# sheet_V2.net
KiCad netlist of a schematic drawn in Altium Designer
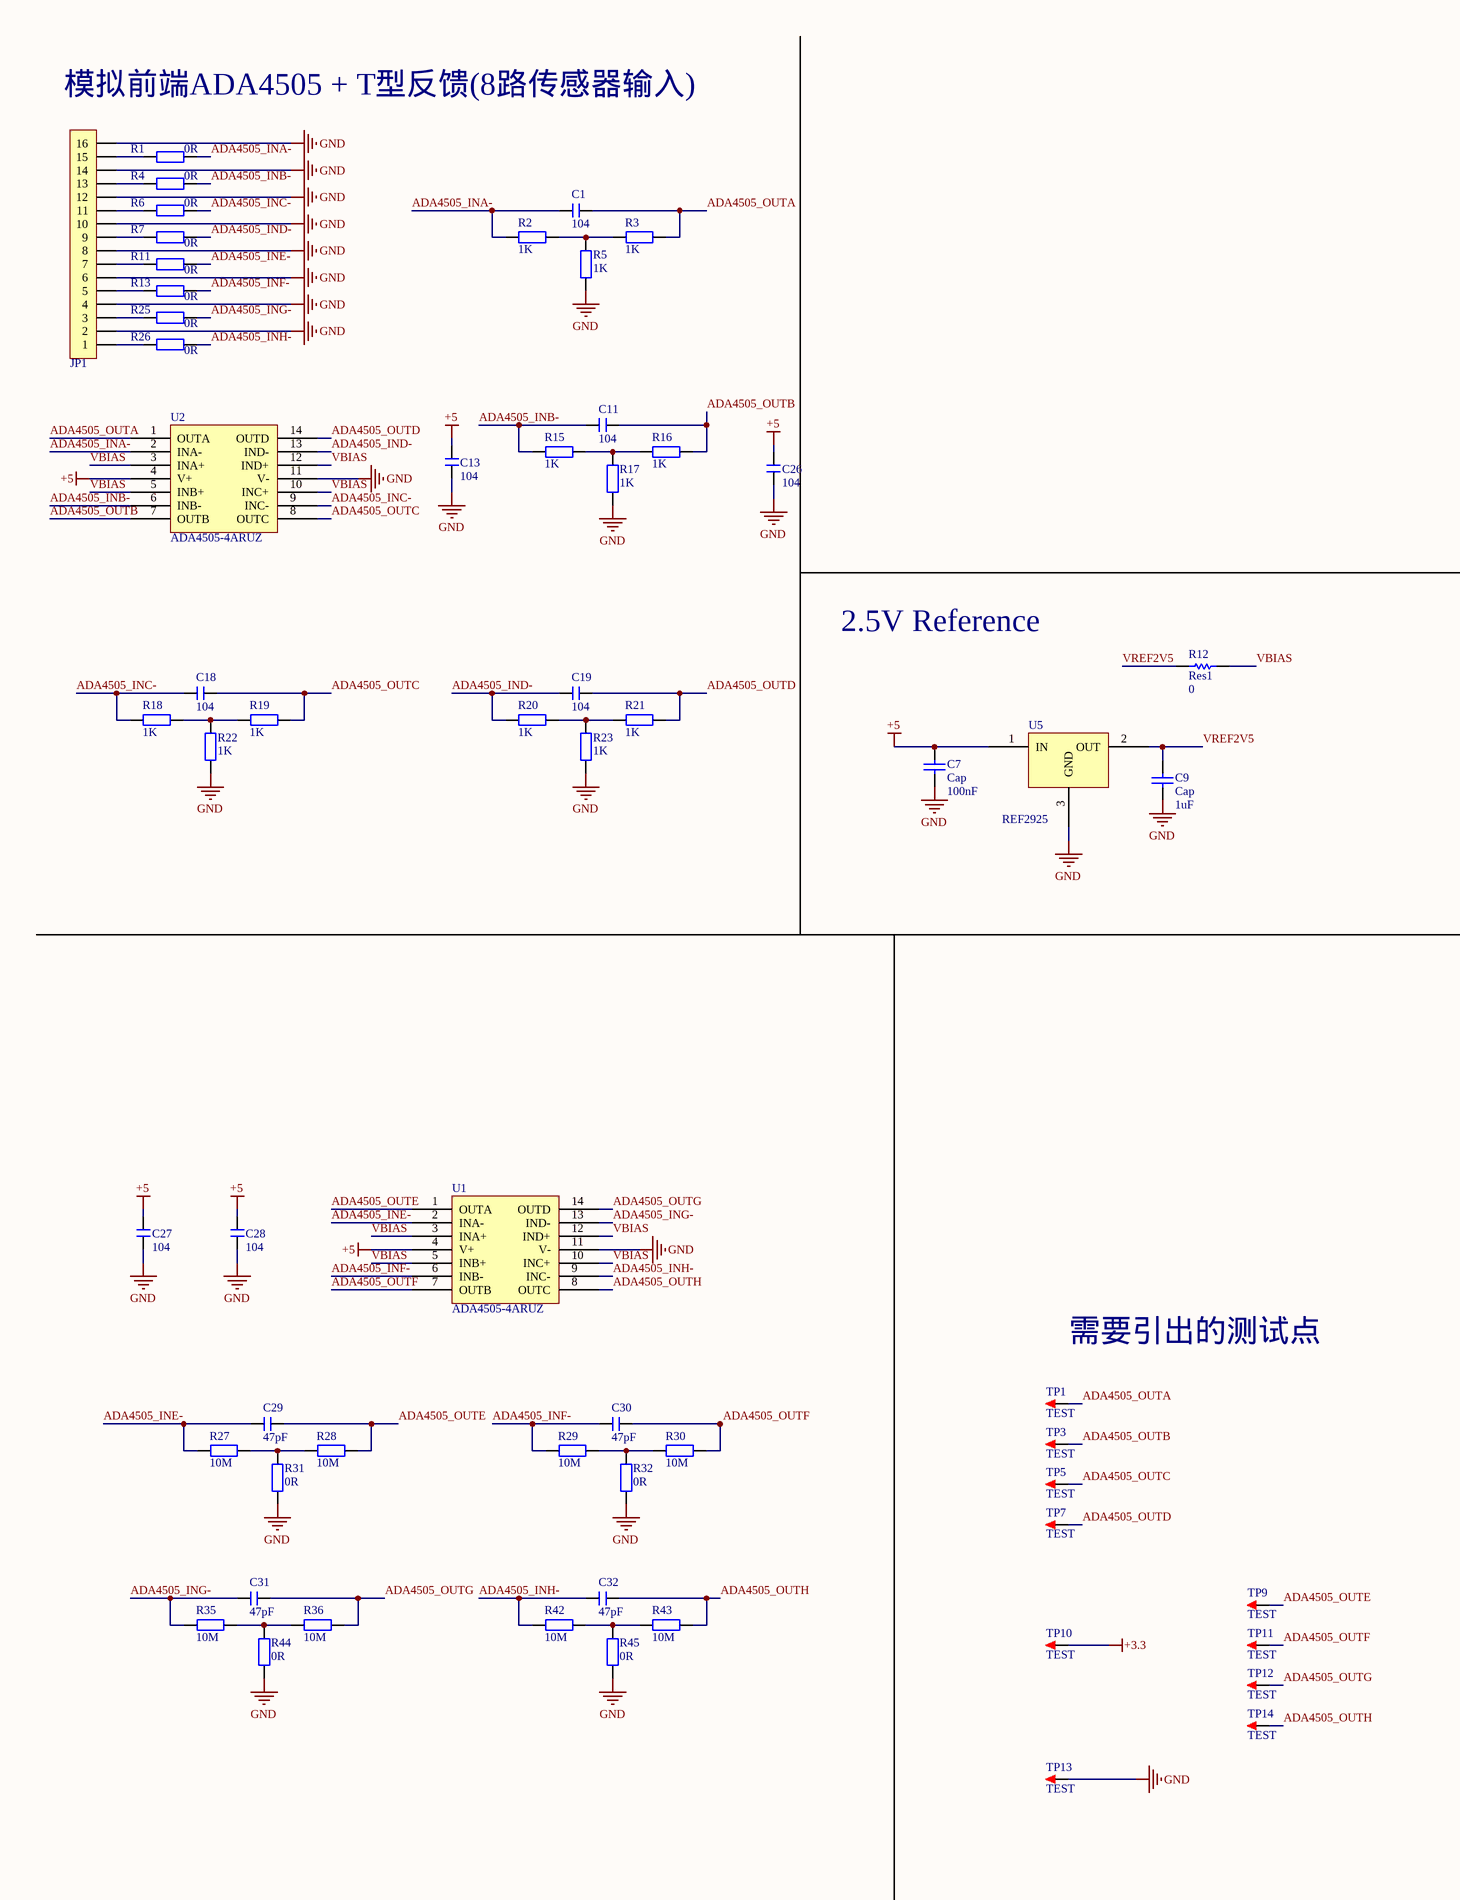
[diagram p0: sheet_V2.SchDoc, left]
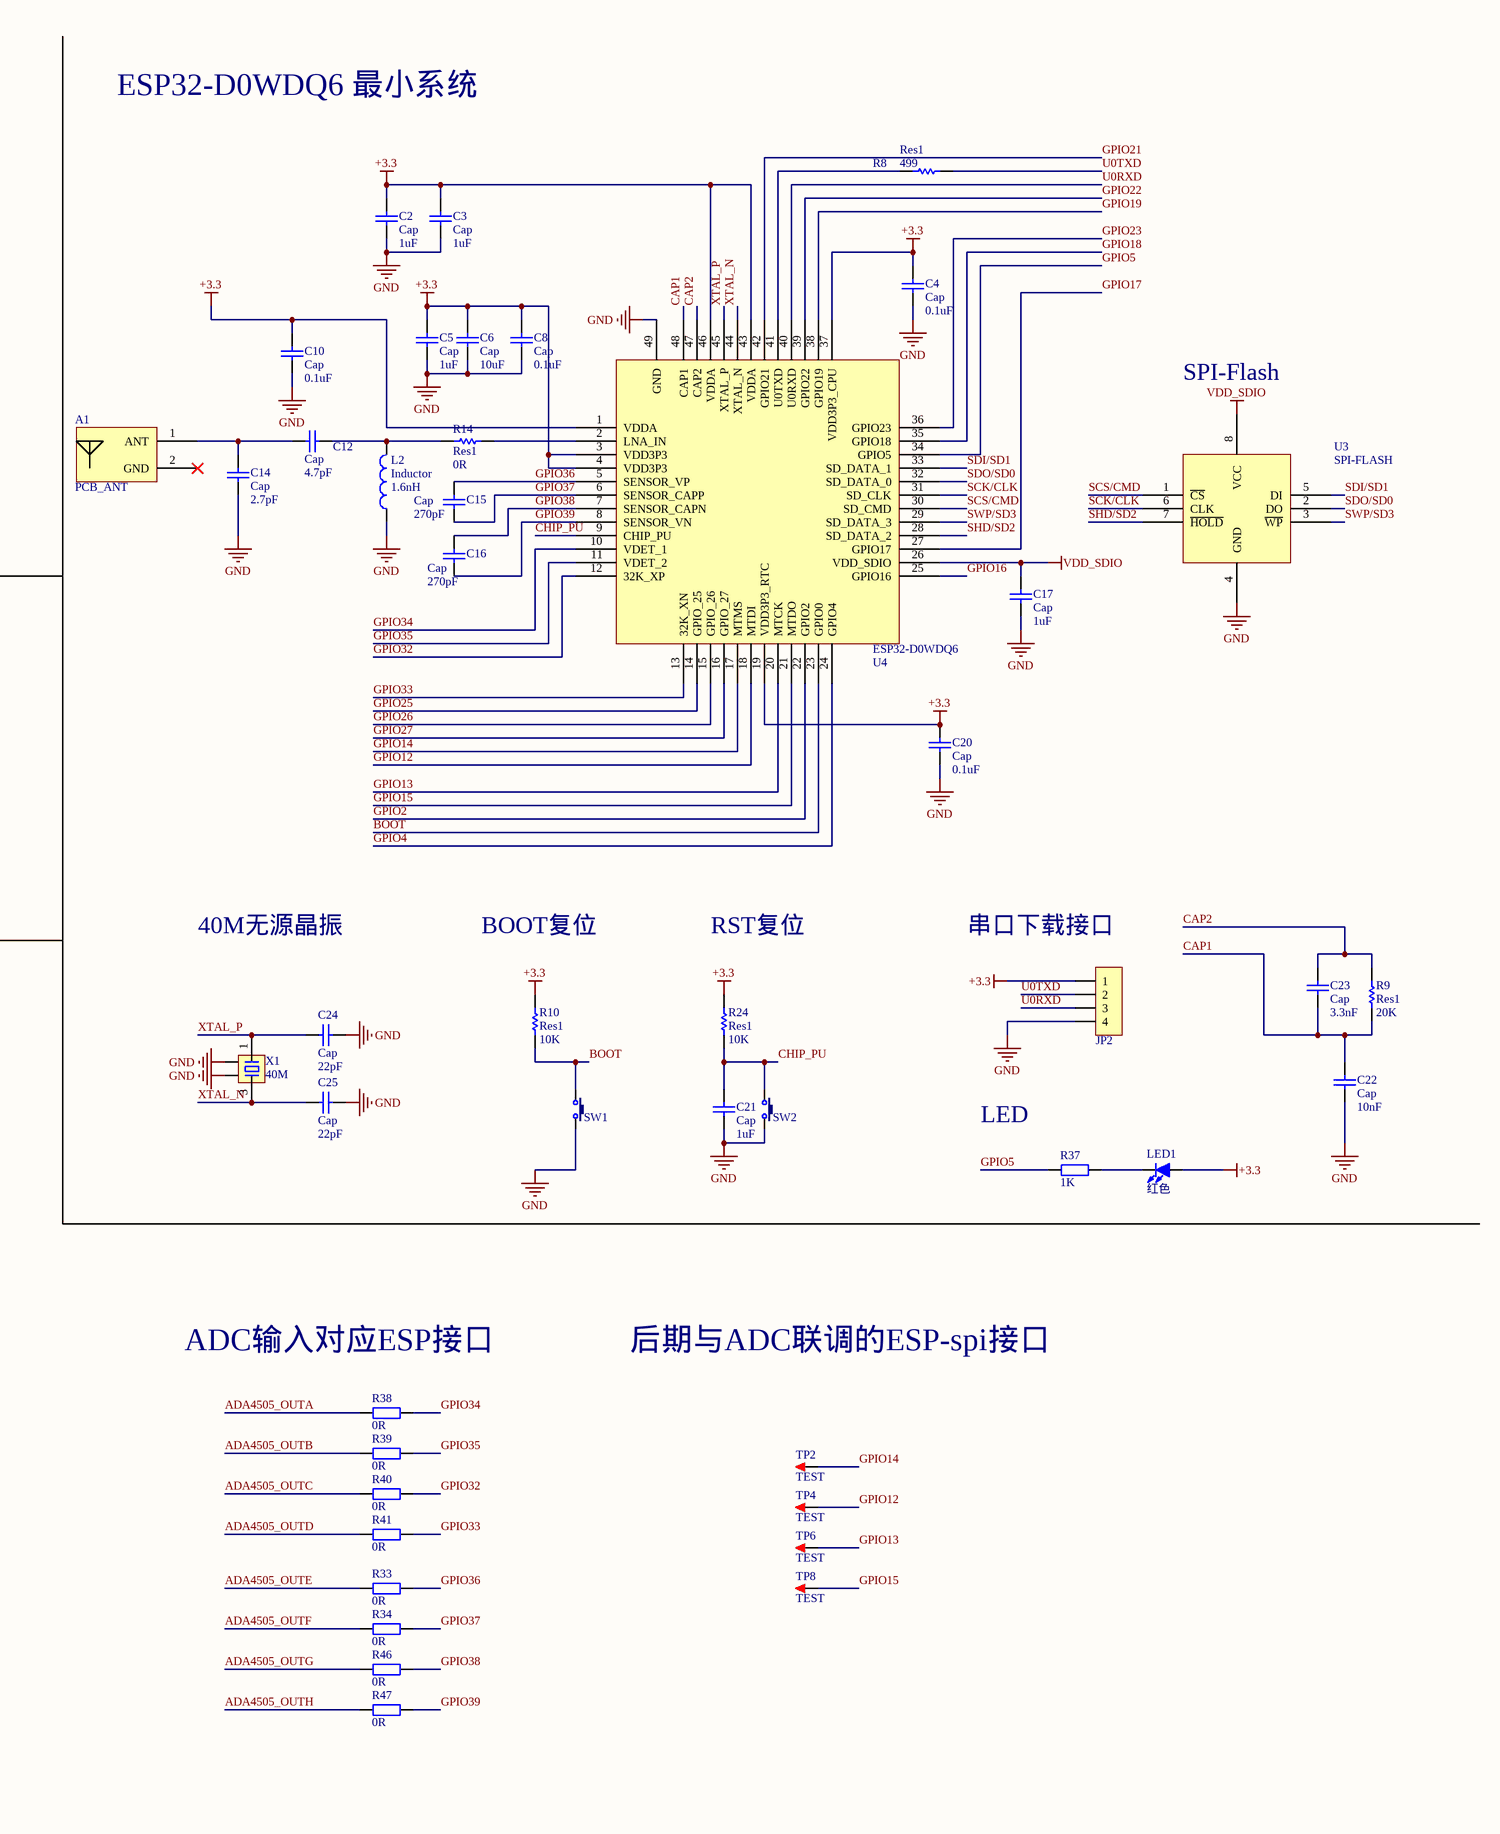
[diagram p1: sheet_V2.SchDoc, right]

(export (version "E")
  (design (tool "Eeschema 10.0.6"))
  (components
    (comp (ref "A1")
      (value "PCB_ANT")
      (footprint "PCB_ANT")
      (description "2.4G-esp32")
      (libsource (lib "Schlib1") (part "PCB_ANT"))
    )
    (comp (ref "C1")
      (value "104")
      (footprint "C 0402_L")
      (description "无极性贴片电容")
      (fields (field (name "版权归属") "源创客"))
      (libsource (lib "Basic_Integrated_Library") (part "C"))
    )
    (comp (ref "C2")
      (value "Cap")
      (footprint "C 0402_L")
      (description "Capacitor")
      (fields (field (name "ALTIUM_VALUE") "1uF") (field (name "PUBLISHER") "Altium Limited"))
      (libsource (lib "Miscellaneous Devices") (part "Cap"))
    )
    (comp (ref "C3")
      (value "Cap")
      (footprint "C 0402_L")
      (description "Capacitor")
      (fields (field (name "ALTIUM_VALUE") "1uF") (field (name "PUBLISHER") "Altium Limited"))
      (libsource (lib "Miscellaneous Devices") (part "Cap"))
    )
    (comp (ref "C4")
      (value "Cap")
      (footprint "C 0402_L")
      (description "Capacitor")
      (fields (field (name "ALTIUM_VALUE") "0.1uF") (field (name "PUBLISHER") "Altium Limited"))
      (libsource (lib "Miscellaneous Devices") (part "Cap"))
    )
    (comp (ref "C5")
      (value "Cap")
      (footprint "C 0402_L")
      (description "Capacitor")
      (fields (field (name "ALTIUM_VALUE") "1uF") (field (name "PUBLISHER") "Altium Limited"))
      (libsource (lib "Miscellaneous Devices") (part "Cap"))
    )
    (comp (ref "C6")
      (value "Cap")
      (footprint "C 0402_L")
      (description "Capacitor")
      (fields (field (name "ALTIUM_VALUE") "10uF") (field (name "PUBLISHER") "Altium Limited"))
      (libsource (lib "Miscellaneous Devices") (part "Cap"))
    )
    (comp (ref "C7")
      (value "Cap")
      (footprint "C 0402_L")
      (description "Capacitor")
      (fields (field (name "ALTIUM_VALUE") "100nF") (field (name "PUBLISHER") "Altium Limited"))
      (libsource (lib "Miscellaneous Devices") (part "Cap"))
    )
    (comp (ref "C8")
      (value "Cap")
      (footprint "C 0402_L")
      (description "Capacitor")
      (fields (field (name "ALTIUM_VALUE") "0.1uF") (field (name "PUBLISHER") "Altium Limited"))
      (libsource (lib "Miscellaneous Devices") (part "Cap"))
    )
    (comp (ref "C9")
      (value "Cap")
      (footprint "C 0402_L")
      (description "Capacitor")
      (fields (field (name "ALTIUM_VALUE") "1uF") (field (name "PUBLISHER") "Altium Limited"))
      (libsource (lib "Miscellaneous Devices") (part "Cap"))
    )
    (comp (ref "C10")
      (value "Cap")
      (footprint "C 0402_L")
      (description "Capacitor")
      (fields (field (name "ALTIUM_VALUE") "0.1uF") (field (name "PUBLISHER") "Altium Limited"))
      (libsource (lib "Miscellaneous Devices") (part "Cap"))
    )
    (comp (ref "C11")
      (value "104")
      (footprint "C 0402_L")
      (description "无极性贴片电容")
      (fields (field (name "版权归属") "源创客"))
      (libsource (lib "Basic_Integrated_Library") (part "C"))
    )
    (comp (ref "C12")
      (value "Cap")
      (footprint "C 0402_L")
      (description "Capacitor")
      (fields (field (name "ALTIUM_VALUE") "4.7pF") (field (name "PUBLISHER") "Altium Limited"))
      (libsource (lib "Miscellaneous Devices") (part "Cap"))
    )
    (comp (ref "C13")
      (value "104")
      (footprint "C 0402_L")
      (description "无极性贴片电容")
      (fields (field (name "版权归属") "源创客"))
      (libsource (lib "Basic_Integrated_Library") (part "C"))
    )
    (comp (ref "C14")
      (value "Cap")
      (footprint "C 0402_L")
      (description "Capacitor")
      (fields (field (name "ALTIUM_VALUE") "2.7pF") (field (name "PUBLISHER") "Altium Limited"))
      (libsource (lib "Miscellaneous Devices") (part "Cap"))
    )
    (comp (ref "C15")
      (value "Cap")
      (footprint "C 0402_L")
      (description "Capacitor")
      (fields (field (name "ALTIUM_VALUE") "270pF") (field (name "PUBLISHER") "Altium Limited"))
      (libsource (lib "Miscellaneous Devices") (part "Cap"))
    )
    (comp (ref "C16")
      (value "Cap")
      (footprint "C 0402_L")
      (description "Capacitor")
      (fields (field (name "ALTIUM_VALUE") "270pF") (field (name "PUBLISHER") "Altium Limited"))
      (libsource (lib "Miscellaneous Devices") (part "Cap"))
    )
    (comp (ref "C17")
      (value "Cap")
      (footprint "C 0402_L")
      (description "Capacitor")
      (fields (field (name "ALTIUM_VALUE") "1uF") (field (name "PUBLISHER") "Altium Limited"))
      (libsource (lib "Miscellaneous Devices") (part "Cap"))
    )
    (comp (ref "C18")
      (value "104")
      (footprint "C 0402_L")
      (description "无极性贴片电容")
      (fields (field (name "版权归属") "源创客"))
      (libsource (lib "Basic_Integrated_Library") (part "C"))
    )
    (comp (ref "C19")
      (value "104")
      (footprint "C 0402_L")
      (description "无极性贴片电容")
      (fields (field (name "版权归属") "源创客"))
      (libsource (lib "Basic_Integrated_Library") (part "C"))
    )
    (comp (ref "C20")
      (value "Cap")
      (footprint "C 0402_L")
      (description "Capacitor")
      (fields (field (name "ALTIUM_VALUE") "0.1uF") (field (name "PUBLISHER") "Altium Limited"))
      (libsource (lib "Miscellaneous Devices") (part "Cap"))
    )
    (comp (ref "C21")
      (value "Cap")
      (footprint "C 0402_L")
      (description "Capacitor")
      (fields (field (name "ALTIUM_VALUE") "1uF") (field (name "PUBLISHER") "Altium Limited"))
      (libsource (lib "Miscellaneous Devices") (part "Cap"))
    )
    (comp (ref "C22")
      (value "Cap")
      (footprint "C 0402_L")
      (description "Capacitor")
      (fields (field (name "ALTIUM_VALUE") "10nF") (field (name "PUBLISHER") "Altium Limited"))
      (libsource (lib "Miscellaneous Devices") (part "Cap"))
    )
    (comp (ref "C23")
      (value "Cap")
      (footprint "C 0402_L")
      (description "Capacitor")
      (fields (field (name "ALTIUM_VALUE") "3.3nF") (field (name "PUBLISHER") "Altium Limited"))
      (libsource (lib "Miscellaneous Devices") (part "Cap"))
    )
    (comp (ref "C24")
      (value "Cap")
      (footprint "C 0402_L")
      (description "Capacitor")
      (fields (field (name "ALTIUM_VALUE") "22pF") (field (name "PUBLISHER") "Altium Limited"))
      (libsource (lib "Miscellaneous Devices") (part "Cap"))
    )
    (comp (ref "C25")
      (value "Cap")
      (footprint "C 0402_L")
      (description "Capacitor")
      (fields (field (name "ALTIUM_VALUE") "22pF") (field (name "PUBLISHER") "Altium Limited"))
      (libsource (lib "Miscellaneous Devices") (part "Cap"))
    )
    (comp (ref "C26")
      (value "104")
      (footprint "C 0402_L")
      (description "无极性贴片电容")
      (fields (field (name "版权归属") "源创客"))
      (libsource (lib "Basic_Integrated_Library") (part "C"))
    )
    (comp (ref "C27")
      (value "104")
      (footprint "C 0402_L")
      (description "无极性贴片电容")
      (fields (field (name "版权归属") "源创客"))
      (libsource (lib "Basic_Integrated_Library") (part "C"))
    )
    (comp (ref "C28")
      (value "104")
      (footprint "C 0402_L")
      (description "无极性贴片电容")
      (fields (field (name "版权归属") "源创客"))
      (libsource (lib "Basic_Integrated_Library") (part "C"))
    )
    (comp (ref "C29")
      (value "47pF")
      (footprint "C 0402_L")
      (description "无极性贴片电容")
      (fields (field (name "版权归属") "源创客"))
      (libsource (lib "Basic_Integrated_Library") (part "C"))
    )
    (comp (ref "C30")
      (value "47pF")
      (footprint "C 0402_L")
      (description "无极性贴片电容")
      (fields (field (name "版权归属") "源创客"))
      (libsource (lib "Basic_Integrated_Library") (part "C"))
    )
    (comp (ref "C31")
      (value "47pF")
      (footprint "C 0402_L")
      (description "无极性贴片电容")
      (fields (field (name "版权归属") "源创客"))
      (libsource (lib "Basic_Integrated_Library") (part "C"))
    )
    (comp (ref "C32")
      (value "47pF")
      (footprint "C 0402_L")
      (description "无极性贴片电容")
      (fields (field (name "版权归属") "源创客"))
      (libsource (lib "Basic_Integrated_Library") (part "C"))
    )
    (comp (ref "JP1")
      (value "HDR-1X16")
      (footprint "FPC0.5 2H-WS-16P")
      (description "16P接插件")
      (fields (field (name "版权归属") "源创客"))
      (libsource (lib "Basic_Integrated_Library") (part "Header 16"))
    )
    (comp (ref "JP2")
      (value "HDR-1X4")
      (footprint "2.54_pad_4")
      (description "4P接插件")
      (fields (field (name "版权归属") "源创客"))
      (libsource (lib "Basic_Integrated_Library") (part "Header 4"))
    )
    (comp (ref "L2")
      (value "Inductor")
      (footprint "L 0402")
      (fields (field (name "ALTIUM_VALUE") "1.6nH") (field (name "PUBLISHER") "Altium Limited"))
      (libsource (lib "Miscellaneous Devices") (part "Inductor"))
    )
    (comp (ref "LED1")
      (value "红色")
      (footprint "LED 0603R")
      (description "贴片LED")
      (fields (field (name "版权归属") "源创客"))
      (libsource (lib "Basic_Integrated_Library") (part "LED-SMD"))
    )
    (comp (ref "R1")
      (value "0R")
      (footprint "R 0402_L")
      (description "贴片电阻")
      (fields (field (name "版权归属") "源创客"))
      (libsource (lib "Basic_Integrated_Library") (part "R"))
    )
    (comp (ref "R2")
      (value "1K")
      (footprint "R 0805_L")
      (description "贴片电阻")
      (fields (field (name "版权归属") "源创客"))
      (libsource (lib "Basic_Integrated_Library") (part "R"))
    )
    (comp (ref "R3")
      (value "1K")
      (footprint "R 0805_L")
      (description "贴片电阻")
      (fields (field (name "版权归属") "源创客"))
      (libsource (lib "Basic_Integrated_Library") (part "R"))
    )
    (comp (ref "R4")
      (value "0R")
      (footprint "R 0402_L")
      (description "贴片电阻")
      (fields (field (name "版权归属") "源创客"))
      (libsource (lib "Basic_Integrated_Library") (part "R"))
    )
    (comp (ref "R5")
      (value "1K")
      (footprint "R 0805_L")
      (description "贴片电阻")
      (fields (field (name "版权归属") "源创客"))
      (libsource (lib "Basic_Integrated_Library") (part "R"))
    )
    (comp (ref "R6")
      (value "0R")
      (footprint "R 0402_L")
      (description "贴片电阻")
      (fields (field (name "版权归属") "源创客"))
      (libsource (lib "Basic_Integrated_Library") (part "R"))
    )
    (comp (ref "R7")
      (value "0R")
      (footprint "R 0402_L")
      (description "贴片电阻")
      (fields (field (name "版权归属") "源创客"))
      (libsource (lib "Basic_Integrated_Library") (part "R"))
    )
    (comp (ref "R8")
      (value "Res1")
      (footprint "R 0402_L")
      (description "Resistor")
      (fields (field (name "ALTIUM_VALUE") "499") (field (name "PUBLISHER") "Altium Limited"))
      (libsource (lib "Miscellaneous Devices") (part "Res1"))
    )
    (comp (ref "R9")
      (value "Res1")
      (footprint "R 0402_L")
      (description "Resistor")
      (fields (field (name "ALTIUM_VALUE") "20K") (field (name "PUBLISHER") "Altium Limited"))
      (libsource (lib "Miscellaneous Devices") (part "Res1"))
    )
    (comp (ref "R10")
      (value "Res1")
      (footprint "R 0402_L")
      (description "Resistor")
      (fields (field (name "ALTIUM_VALUE") "10K") (field (name "PUBLISHER") "Altium Limited"))
      (libsource (lib "Miscellaneous Devices") (part "Res1"))
    )
    (comp (ref "R11")
      (value "0R")
      (footprint "R 0402_L")
      (description "贴片电阻")
      (fields (field (name "版权归属") "源创客"))
      (libsource (lib "Basic_Integrated_Library") (part "R"))
    )
    (comp (ref "R12")
      (value "Res1")
      (footprint "R 0402_L")
      (description "Resistor")
      (fields (field (name "ALTIUM_VALUE") "0") (field (name "PUBLISHER") "Altium Limited"))
      (libsource (lib "Miscellaneous Devices") (part "Res1"))
    )
    (comp (ref "R13")
      (value "0R")
      (footprint "R 0402_L")
      (description "贴片电阻")
      (fields (field (name "版权归属") "源创客"))
      (libsource (lib "Basic_Integrated_Library") (part "R"))
    )
    (comp (ref "R14")
      (value "Res1")
      (footprint "R 0402_L")
      (description "Resistor")
      (fields (field (name "ALTIUM_VALUE") "0R") (field (name "PUBLISHER") "Altium Limited"))
      (libsource (lib "Miscellaneous Devices") (part "Res1"))
    )
    (comp (ref "R15")
      (value "1K")
      (footprint "R 0805_L")
      (description "贴片电阻")
      (fields (field (name "版权归属") "源创客"))
      (libsource (lib "Basic_Integrated_Library") (part "R"))
    )
    (comp (ref "R16")
      (value "1K")
      (footprint "R 0805_L")
      (description "贴片电阻")
      (fields (field (name "版权归属") "源创客"))
      (libsource (lib "Basic_Integrated_Library") (part "R"))
    )
    (comp (ref "R17")
      (value "1K")
      (footprint "R 0805_L")
      (description "贴片电阻")
      (fields (field (name "版权归属") "源创客"))
      (libsource (lib "Basic_Integrated_Library") (part "R"))
    )
    (comp (ref "R18")
      (value "1K")
      (footprint "R 0805_L")
      (description "贴片电阻")
      (fields (field (name "版权归属") "源创客"))
      (libsource (lib "Basic_Integrated_Library") (part "R"))
    )
    (comp (ref "R19")
      (value "1K")
      (footprint "R 0805_L")
      (description "贴片电阻")
      (fields (field (name "版权归属") "源创客"))
      (libsource (lib "Basic_Integrated_Library") (part "R"))
    )
    (comp (ref "R20")
      (value "1K")
      (footprint "R 0805_L")
      (description "贴片电阻")
      (fields (field (name "版权归属") "源创客"))
      (libsource (lib "Basic_Integrated_Library") (part "R"))
    )
    (comp (ref "R21")
      (value "1K")
      (footprint "R 0805_L")
      (description "贴片电阻")
      (fields (field (name "版权归属") "源创客"))
      (libsource (lib "Basic_Integrated_Library") (part "R"))
    )
    (comp (ref "R22")
      (value "1K")
      (footprint "R 0805_L")
      (description "贴片电阻")
      (fields (field (name "版权归属") "源创客"))
      (libsource (lib "Basic_Integrated_Library") (part "R"))
    )
    (comp (ref "R23")
      (value "1K")
      (footprint "R 0805_L")
      (description "贴片电阻")
      (fields (field (name "版权归属") "源创客"))
      (libsource (lib "Basic_Integrated_Library") (part "R"))
    )
    (comp (ref "R24")
      (value "Res1")
      (footprint "R 0402_L")
      (description "Resistor")
      (fields (field (name "ALTIUM_VALUE") "10K") (field (name "PUBLISHER") "Altium Limited"))
      (libsource (lib "Miscellaneous Devices") (part "Res1"))
    )
    (comp (ref "R25")
      (value "0R")
      (footprint "R 0402_L")
      (description "贴片电阻")
      (fields (field (name "版权归属") "源创客"))
      (libsource (lib "Basic_Integrated_Library") (part "R"))
    )
    (comp (ref "R26")
      (value "0R")
      (footprint "R 0402_L")
      (description "贴片电阻")
      (fields (field (name "版权归属") "源创客"))
      (libsource (lib "Basic_Integrated_Library") (part "R"))
    )
    (comp (ref "R27")
      (value "10M")
      (footprint "R 0805_L")
      (description "贴片电阻")
      (fields (field (name "版权归属") "源创客"))
      (libsource (lib "Basic_Integrated_Library") (part "R"))
    )
    (comp (ref "R28")
      (value "10M")
      (footprint "R 0805_L")
      (description "贴片电阻")
      (fields (field (name "版权归属") "源创客"))
      (libsource (lib "Basic_Integrated_Library") (part "R"))
    )
    (comp (ref "R29")
      (value "10M")
      (footprint "R 0805_L")
      (description "贴片电阻")
      (fields (field (name "版权归属") "源创客"))
      (libsource (lib "Basic_Integrated_Library") (part "R"))
    )
    (comp (ref "R30")
      (value "10M")
      (footprint "R 0805_L")
      (description "贴片电阻")
      (fields (field (name "版权归属") "源创客"))
      (libsource (lib "Basic_Integrated_Library") (part "R"))
    )
    (comp (ref "R31")
      (value "0R")
      (footprint "R 0805_L")
      (description "贴片电阻")
      (fields (field (name "版权归属") "源创客"))
      (libsource (lib "Basic_Integrated_Library") (part "R"))
    )
    (comp (ref "R32")
      (value "0R")
      (footprint "R 0805_L")
      (description "贴片电阻")
      (fields (field (name "版权归属") "源创客"))
      (libsource (lib "Basic_Integrated_Library") (part "R"))
    )
    (comp (ref "R33")
      (value "0R")
      (footprint "R 0402_L")
      (description "贴片电阻")
      (fields (field (name "版权归属") "源创客"))
      (libsource (lib "Basic_Integrated_Library") (part "R"))
    )
    (comp (ref "R34")
      (value "0R")
      (footprint "R 0402_L")
      (description "贴片电阻")
      (fields (field (name "版权归属") "源创客"))
      (libsource (lib "Basic_Integrated_Library") (part "R"))
    )
    (comp (ref "R35")
      (value "10M")
      (footprint "R 0805_L")
      (description "贴片电阻")
      (fields (field (name "版权归属") "源创客"))
      (libsource (lib "Basic_Integrated_Library") (part "R"))
    )
    (comp (ref "R36")
      (value "10M")
      (footprint "R 0805_L")
      (description "贴片电阻")
      (fields (field (name "版权归属") "源创客"))
      (libsource (lib "Basic_Integrated_Library") (part "R"))
    )
    (comp (ref "R37")
      (value "1K")
      (footprint "R 0402_L")
      (description "贴片电阻")
      (fields (field (name "版权归属") "源创客"))
      (libsource (lib "Basic_Integrated_Library") (part "R"))
    )
    (comp (ref "R38")
      (value "0R")
      (footprint "R 0402_L")
      (description "贴片电阻")
      (fields (field (name "版权归属") "源创客"))
      (libsource (lib "Basic_Integrated_Library") (part "R"))
    )
    (comp (ref "R39")
      (value "0R")
      (footprint "R 0402_L")
      (description "贴片电阻")
      (fields (field (name "版权归属") "源创客"))
      (libsource (lib "Basic_Integrated_Library") (part "R"))
    )
    (comp (ref "R40")
      (value "0R")
      (footprint "R 0402_L")
      (description "贴片电阻")
      (fields (field (name "版权归属") "源创客"))
      (libsource (lib "Basic_Integrated_Library") (part "R"))
    )
    (comp (ref "R41")
      (value "0R")
      (footprint "R 0402_L")
      (description "贴片电阻")
      (fields (field (name "版权归属") "源创客"))
      (libsource (lib "Basic_Integrated_Library") (part "R"))
    )
    (comp (ref "R42")
      (value "10M")
      (footprint "R 0805_L")
      (description "贴片电阻")
      (fields (field (name "版权归属") "源创客"))
      (libsource (lib "Basic_Integrated_Library") (part "R"))
    )
    (comp (ref "R43")
      (value "10M")
      (footprint "R 0805_L")
      (description "贴片电阻")
      (fields (field (name "版权归属") "源创客"))
      (libsource (lib "Basic_Integrated_Library") (part "R"))
    )
    (comp (ref "R44")
      (value "0R")
      (footprint "R 0805_L")
      (description "贴片电阻")
      (fields (field (name "版权归属") "源创客"))
      (libsource (lib "Basic_Integrated_Library") (part "R"))
    )
    (comp (ref "R45")
      (value "0R")
      (footprint "R 0805_L")
      (description "贴片电阻")
      (fields (field (name "版权归属") "源创客"))
      (libsource (lib "Basic_Integrated_Library") (part "R"))
    )
    (comp (ref "R46")
      (value "0R")
      (footprint "R 0402_L")
      (description "贴片电阻")
      (fields (field (name "版权归属") "源创客"))
      (libsource (lib "Basic_Integrated_Library") (part "R"))
    )
    (comp (ref "R47")
      (value "0R")
      (footprint "R 0402_L")
      (description "贴片电阻")
      (fields (field (name "版权归属") "源创客"))
      (libsource (lib "Basic_Integrated_Library") (part "R"))
    )
    (comp (ref "SW1")
      (value "3x6x5")
      (footprint "KEY-little")
      (description "3x6轻触开关")
      (fields (field (name "版权归属") "源创客"))
      (libsource (lib "5.1   - 按键-开关") (part "TSW 3x6"))
    )
    (comp (ref "SW2")
      (value "3x6x5")
      (footprint "KEY-little")
      (description "3x6轻触开关")
      (fields (field (name "版权归属") "源创客"))
      (libsource (lib "5.1   - 按键-开关") (part "TSW 3x6"))
    )
    (comp (ref "TP1")
      (value "TEST")
      (footprint "TEST 0.8")
      (description "测试点")
      (fields (field (name "版权归属") "源创客"))
      (libsource (lib "Basic_Integrated_Library") (part "TEST"))
    )
    (comp (ref "TP2")
      (value "TEST")
      (footprint "TEST 0.8")
      (description "测试点")
      (fields (field (name "版权归属") "源创客"))
      (libsource (lib "Basic_Integrated_Library") (part "TEST"))
    )
    (comp (ref "TP3")
      (value "TEST")
      (footprint "TEST 0.8")
      (description "测试点")
      (fields (field (name "版权归属") "源创客"))
      (libsource (lib "Basic_Integrated_Library") (part "TEST"))
    )
    (comp (ref "TP4")
      (value "TEST")
      (footprint "TEST 0.8")
      (description "测试点")
      (fields (field (name "版权归属") "源创客"))
      (libsource (lib "Basic_Integrated_Library") (part "TEST"))
    )
    (comp (ref "TP5")
      (value "TEST")
      (footprint "TEST 0.8")
      (description "测试点")
      (fields (field (name "版权归属") "源创客"))
      (libsource (lib "Basic_Integrated_Library") (part "TEST"))
    )
    (comp (ref "TP6")
      (value "TEST")
      (footprint "TEST 0.8")
      (description "测试点")
      (fields (field (name "版权归属") "源创客"))
      (libsource (lib "Basic_Integrated_Library") (part "TEST"))
    )
    (comp (ref "TP7")
      (value "TEST")
      (footprint "TEST 0.8")
      (description "测试点")
      (fields (field (name "版权归属") "源创客"))
      (libsource (lib "Basic_Integrated_Library") (part "TEST"))
    )
    (comp (ref "TP8")
      (value "TEST")
      (footprint "TEST 0.8")
      (description "测试点")
      (fields (field (name "版权归属") "源创客"))
      (libsource (lib "Basic_Integrated_Library") (part "TEST"))
    )
    (comp (ref "TP9")
      (value "TEST")
      (footprint "TEST 0.8")
      (description "测试点")
      (fields (field (name "版权归属") "源创客"))
      (libsource (lib "Basic_Integrated_Library") (part "TEST"))
    )
    (comp (ref "TP10")
      (value "TEST")
      (footprint "TEST 0.8")
      (description "测试点")
      (fields (field (name "版权归属") "源创客"))
      (libsource (lib "Basic_Integrated_Library") (part "TEST"))
    )
    (comp (ref "TP11")
      (value "TEST")
      (footprint "TEST 0.8")
      (description "测试点")
      (fields (field (name "版权归属") "源创客"))
      (libsource (lib "Basic_Integrated_Library") (part "TEST"))
    )
    (comp (ref "TP12")
      (value "TEST")
      (footprint "TEST 0.8")
      (description "测试点")
      (fields (field (name "版权归属") "源创客"))
      (libsource (lib "Basic_Integrated_Library") (part "TEST"))
    )
    (comp (ref "TP13")
      (value "TEST")
      (footprint "TEST 0.8")
      (description "测试点")
      (fields (field (name "版权归属") "源创客"))
      (libsource (lib "Basic_Integrated_Library") (part "TEST"))
    )
    (comp (ref "TP14")
      (value "TEST")
      (footprint "TEST 0.8")
      (description "测试点")
      (fields (field (name "版权归属") "源创客"))
      (libsource (lib "Basic_Integrated_Library") (part "TEST"))
    )
    (comp (ref "U1")
      (value "ADA4505-4ARUZ")
      (footprint "ADA4505-4ARUZ")
      (libsource (lib "Schlib1") (part "ADA4505-4ARUZ"))
    )
    (comp (ref "U2")
      (value "ADA4505-4ARUZ")
      (footprint "ADA4505-4ARUZ")
      (libsource (lib "Schlib1") (part "ADA4505-4ARUZ"))
    )
    (comp (ref "U3")
      (value "SPI-FLASH")
      (footprint "SPI-Flash")
      (libsource (lib "Schlib1") (part "SPI-FLASH"))
    )
    (comp (ref "U4")
      (value "ESP32-D0WDQ6")
      (footprint "ESP32D0WDQ6")
      (libsource (lib "Schlib1") (part "ESP32-D0WDQ6"))
    )
    (comp (ref "U5")
      (value "REF2925")
      (footprint "REF2925AIDBZR")
      (description "2.5V reference")
      (libsource (lib "Schlib1") (part "REF2925"))
    )
    (comp (ref "X1")
      (value "40M")
      (footprint "晶振3225")
      (description "4脚无源晶振")
      (fields (field (name "版权归属") "源创客"))
      (libsource (lib "晶体振荡器") (part "XTAL-4P"))
    )
  )
  (nets
    (net (code "1") (name "+3.3") (class "Default")
      (node (ref "C10") (pin "2") (pinfunction "2_2") (pintype "passive"))
      (node (ref "C2") (pin "2") (pinfunction "2_2") (pintype "passive"))
      (node (ref "C20") (pin "2") (pinfunction "2_2") (pintype "passive"))
      (node (ref "C3") (pin "2") (pinfunction "2_2") (pintype "passive"))
      (node (ref "C4") (pin "2") (pinfunction "2_2") (pintype "passive"))
      (node (ref "C5") (pin "2") (pinfunction "2_2") (pintype "passive"))
      (node (ref "C6") (pin "2") (pinfunction "2_2") (pintype "passive"))
      (node (ref "C8") (pin "2") (pinfunction "2_2") (pintype "passive"))
      (node (ref "JP2") (pin "1") (pinfunction "1_1") (pintype "passive"))
      (node (ref "LED1") (pin "1") (pinfunction "A_1") (pintype "passive"))
      (node (ref "R10") (pin "2") (pinfunction "2_2") (pintype "passive"))
      (node (ref "R24") (pin "2") (pinfunction "2_2") (pintype "passive"))
      (node (ref "TP10") (pin "1") (pinfunction "1_1") (pintype "passive"))
      (node (ref "U4") (pin "1") (pinfunction "VDDA_1") (pintype "passive"))
      (node (ref "U4") (pin "19") (pinfunction "VDD3P3_RTC_19") (pintype "passive"))
      (node (ref "U4") (pin "3") (pinfunction "VDD3P3_3") (pintype "passive"))
      (node (ref "U4") (pin "37") (pinfunction "VDD3P3_CPU_37") (pintype "passive"))
      (node (ref "U4") (pin "4") (pinfunction "VDD3P3_4") (pintype "passive"))
      (node (ref "U4") (pin "43") (pinfunction "VDDA_43") (pintype "passive"))
      (node (ref "U4") (pin "46") (pinfunction "VDDA_46") (pintype "passive"))
    )
    (net (code "2") (name "+5") (class "Default")
      (node (ref "C13") (pin "2") (pinfunction "2_2") (pintype "passive"))
      (node (ref "C26") (pin "2") (pinfunction "2_2") (pintype "passive"))
      (node (ref "C27") (pin "2") (pinfunction "2_2") (pintype "passive"))
      (node (ref "C28") (pin "2") (pinfunction "2_2") (pintype "passive"))
      (node (ref "C7") (pin "2") (pinfunction "2_2") (pintype "passive"))
      (node (ref "U1") (pin "4") (pinfunction "V+_4") (pintype "passive"))
      (node (ref "U2") (pin "4") (pinfunction "V+_4") (pintype "passive"))
      (node (ref "U5") (pin "1") (pinfunction "IN_1") (pintype "passive"))
    )
    (net (code "3") (name "/ADA4505_INA-") (class "Default")
      (node (ref "C1") (pin "1") (pinfunction "1_1") (pintype "passive"))
      (node (ref "R1") (pin "2") (pinfunction "2_2") (pintype "passive"))
      (node (ref "R2") (pin "2") (pinfunction "2_2") (pintype "passive"))
      (node (ref "U2") (pin "2") (pinfunction "INA-_2") (pintype "passive"))
    )
    (net (code "4") (name "/ADA4505_INB-") (class "Default")
      (node (ref "C11") (pin "1") (pinfunction "1_1") (pintype "passive"))
      (node (ref "R15") (pin "2") (pinfunction "2_2") (pintype "passive"))
      (node (ref "R4") (pin "2") (pinfunction "2_2") (pintype "passive"))
      (node (ref "U2") (pin "6") (pinfunction "INB-_6") (pintype "passive"))
    )
    (net (code "5") (name "/ADA4505_INC-") (class "Default")
      (node (ref "C18") (pin "1") (pinfunction "1_1") (pintype "passive"))
      (node (ref "R18") (pin "2") (pinfunction "2_2") (pintype "passive"))
      (node (ref "R6") (pin "2") (pinfunction "2_2") (pintype "passive"))
      (node (ref "U2") (pin "9") (pinfunction "INC-_9") (pintype "passive"))
    )
    (net (code "6") (name "/ADA4505_IND-") (class "Default")
      (node (ref "C19") (pin "1") (pinfunction "1_1") (pintype "passive"))
      (node (ref "R20") (pin "2") (pinfunction "2_2") (pintype "passive"))
      (node (ref "R7") (pin "2") (pinfunction "2_2") (pintype "passive"))
      (node (ref "U2") (pin "13") (pinfunction "IND-_13") (pintype "passive"))
    )
    (net (code "7") (name "/ADA4505_INE-") (class "Default")
      (node (ref "C29") (pin "1") (pinfunction "1_1") (pintype "passive"))
      (node (ref "R11") (pin "2") (pinfunction "2_2") (pintype "passive"))
      (node (ref "R27") (pin "2") (pinfunction "2_2") (pintype "passive"))
      (node (ref "U1") (pin "2") (pinfunction "INA-_2") (pintype "passive"))
    )
    (net (code "8") (name "/ADA4505_INF-") (class "Default")
      (node (ref "C30") (pin "1") (pinfunction "1_1") (pintype "passive"))
      (node (ref "R13") (pin "2") (pinfunction "2_2") (pintype "passive"))
      (node (ref "R29") (pin "2") (pinfunction "2_2") (pintype "passive"))
      (node (ref "U1") (pin "6") (pinfunction "INB-_6") (pintype "passive"))
    )
    (net (code "9") (name "/ADA4505_ING-") (class "Default")
      (node (ref "C31") (pin "1") (pinfunction "1_1") (pintype "passive"))
      (node (ref "R25") (pin "2") (pinfunction "2_2") (pintype "passive"))
      (node (ref "R35") (pin "2") (pinfunction "2_2") (pintype "passive"))
      (node (ref "U1") (pin "13") (pinfunction "IND-_13") (pintype "passive"))
    )
    (net (code "10") (name "/ADA4505_INH-") (class "Default")
      (node (ref "C32") (pin "1") (pinfunction "1_1") (pintype "passive"))
      (node (ref "R26") (pin "2") (pinfunction "2_2") (pintype "passive"))
      (node (ref "R42") (pin "2") (pinfunction "2_2") (pintype "passive"))
      (node (ref "U1") (pin "9") (pinfunction "INC-_9") (pintype "passive"))
    )
    (net (code "11") (name "/ADA4505_OUTA") (class "Default")
      (node (ref "C1") (pin "2") (pinfunction "2_2") (pintype "passive"))
      (node (ref "R3") (pin "1") (pinfunction "1_1") (pintype "passive"))
      (node (ref "R38") (pin "1") (pinfunction "1_1") (pintype "passive"))
      (node (ref "TP1") (pin "1") (pinfunction "1_1") (pintype "passive"))
      (node (ref "U2") (pin "1") (pinfunction "OUTA_1") (pintype "passive"))
    )
    (net (code "12") (name "/ADA4505_OUTB") (class "Default")
      (node (ref "C11") (pin "2") (pinfunction "2_2") (pintype "passive"))
      (node (ref "R16") (pin "1") (pinfunction "1_1") (pintype "passive"))
      (node (ref "R39") (pin "1") (pinfunction "1_1") (pintype "passive"))
      (node (ref "TP3") (pin "1") (pinfunction "1_1") (pintype "passive"))
      (node (ref "U2") (pin "7") (pinfunction "OUTB_7") (pintype "passive"))
    )
    (net (code "13") (name "/ADA4505_OUTC") (class "Default")
      (node (ref "C18") (pin "2") (pinfunction "2_2") (pintype "passive"))
      (node (ref "R19") (pin "1") (pinfunction "1_1") (pintype "passive"))
      (node (ref "R40") (pin "1") (pinfunction "1_1") (pintype "passive"))
      (node (ref "TP5") (pin "1") (pinfunction "1_1") (pintype "passive"))
      (node (ref "U2") (pin "8") (pinfunction "OUTC_8") (pintype "passive"))
    )
    (net (code "14") (name "/ADA4505_OUTD") (class "Default")
      (node (ref "C19") (pin "2") (pinfunction "2_2") (pintype "passive"))
      (node (ref "R21") (pin "1") (pinfunction "1_1") (pintype "passive"))
      (node (ref "R41") (pin "1") (pinfunction "1_1") (pintype "passive"))
      (node (ref "TP7") (pin "1") (pinfunction "1_1") (pintype "passive"))
      (node (ref "U2") (pin "14") (pinfunction "OUTD_14") (pintype "passive"))
    )
    (net (code "15") (name "/ADA4505_OUTE") (class "Default")
      (node (ref "C29") (pin "2") (pinfunction "2_2") (pintype "passive"))
      (node (ref "R28") (pin "1") (pinfunction "1_1") (pintype "passive"))
      (node (ref "R33") (pin "1") (pinfunction "1_1") (pintype "passive"))
      (node (ref "TP9") (pin "1") (pinfunction "1_1") (pintype "passive"))
      (node (ref "U1") (pin "1") (pinfunction "OUTA_1") (pintype "passive"))
    )
    (net (code "16") (name "/ADA4505_OUTF") (class "Default")
      (node (ref "C30") (pin "2") (pinfunction "2_2") (pintype "passive"))
      (node (ref "R30") (pin "1") (pinfunction "1_1") (pintype "passive"))
      (node (ref "R34") (pin "1") (pinfunction "1_1") (pintype "passive"))
      (node (ref "TP11") (pin "1") (pinfunction "1_1") (pintype "passive"))
      (node (ref "U1") (pin "7") (pinfunction "OUTB_7") (pintype "passive"))
    )
    (net (code "17") (name "/ADA4505_OUTG") (class "Default")
      (node (ref "C31") (pin "2") (pinfunction "2_2") (pintype "passive"))
      (node (ref "R36") (pin "1") (pinfunction "1_1") (pintype "passive"))
      (node (ref "R46") (pin "1") (pinfunction "1_1") (pintype "passive"))
      (node (ref "TP12") (pin "1") (pinfunction "1_1") (pintype "passive"))
      (node (ref "U1") (pin "14") (pinfunction "OUTD_14") (pintype "passive"))
    )
    (net (code "18") (name "/ADA4505_OUTH") (class "Default")
      (node (ref "C32") (pin "2") (pinfunction "2_2") (pintype "passive"))
      (node (ref "R43") (pin "1") (pinfunction "1_1") (pintype "passive"))
      (node (ref "R47") (pin "1") (pinfunction "1_1") (pintype "passive"))
      (node (ref "TP14") (pin "1") (pinfunction "1_1") (pintype "passive"))
      (node (ref "U1") (pin "8") (pinfunction "OUTC_8") (pintype "passive"))
    )
    (net (code "19") (name "/BOOT") (class "Default")
      (node (ref "R10") (pin "1") (pinfunction "1_1") (pintype "passive"))
      (node (ref "SW1") (pin "1") (pinfunction "1_1") (pintype "passive"))
      (node (ref "U4") (pin "23") (pinfunction "GPIO0_23") (pintype "passive"))
    )
    (net (code "20") (name "/CAP1") (class "Default")
      (node (ref "C22") (pin "2") (pinfunction "2_2") (pintype "passive"))
      (node (ref "C23") (pin "1") (pinfunction "1_1") (pintype "passive"))
      (node (ref "R9") (pin "1") (pinfunction "1_1") (pintype "passive"))
      (node (ref "U4") (pin "48") (pinfunction "CAP1_48") (pintype "passive"))
    )
    (net (code "21") (name "/CAP2") (class "Default")
      (node (ref "C23") (pin "2") (pinfunction "2_2") (pintype "passive"))
      (node (ref "R9") (pin "2") (pinfunction "2_2") (pintype "passive"))
      (node (ref "U4") (pin "47") (pinfunction "CAP2_47") (pintype "passive"))
    )
    (net (code "22") (name "/CHIP_PU") (class "Default")
      (node (ref "C21") (pin "2") (pinfunction "2_2") (pintype "passive"))
      (node (ref "R24") (pin "1") (pinfunction "1_1") (pintype "passive"))
      (node (ref "SW2") (pin "1") (pinfunction "1_1") (pintype "passive"))
      (node (ref "U4") (pin "9") (pinfunction "CHIP_PU_9") (pintype "passive"))
    )
    (net (code "23") (name "/GPIO2") (class "Default")
      (node (ref "U4") (pin "22") (pinfunction "GPIO2_22") (pintype "passive"))
    )
    (net (code "24") (name "/GPIO4") (class "Default")
      (node (ref "U4") (pin "24") (pinfunction "GPIO4_24") (pintype "passive"))
    )
    (net (code "25") (name "/GPIO5") (class "Default")
      (node (ref "R37") (pin "1") (pinfunction "1_1") (pintype "passive"))
      (node (ref "U4") (pin "34") (pinfunction "GPIO5_34") (pintype "passive"))
    )
    (net (code "26") (name "/GPIO12") (class "Default")
      (node (ref "TP4") (pin "1") (pinfunction "1_1") (pintype "passive"))
      (node (ref "U4") (pin "18") (pinfunction "MTDI_18") (pintype "passive"))
    )
    (net (code "27") (name "/GPIO13") (class "Default")
      (node (ref "TP6") (pin "1") (pinfunction "1_1") (pintype "passive"))
      (node (ref "U4") (pin "20") (pinfunction "MTCK_20") (pintype "passive"))
    )
    (net (code "28") (name "/GPIO14") (class "Default")
      (node (ref "TP2") (pin "1") (pinfunction "1_1") (pintype "passive"))
      (node (ref "U4") (pin "17") (pinfunction "MTMS_17") (pintype "passive"))
    )
    (net (code "29") (name "/GPIO15") (class "Default")
      (node (ref "TP8") (pin "1") (pinfunction "1_1") (pintype "passive"))
      (node (ref "U4") (pin "21") (pinfunction "MTDO_21") (pintype "passive"))
    )
    (net (code "30") (name "/GPIO16") (class "Default")
      (node (ref "U4") (pin "25") (pinfunction "GPIO16_25") (pintype "passive"))
    )
    (net (code "31") (name "/GPIO17") (class "Default")
      (node (ref "U4") (pin "27") (pinfunction "GPIO17_27") (pintype "passive"))
    )
    (net (code "32") (name "/GPIO18") (class "Default")
      (node (ref "U4") (pin "35") (pinfunction "GPIO18_35") (pintype "passive"))
    )
    (net (code "33") (name "/GPIO19") (class "Default")
      (node (ref "U4") (pin "38") (pinfunction "GPIO19_38") (pintype "passive"))
    )
    (net (code "34") (name "/GPIO21") (class "Default")
      (node (ref "U4") (pin "42") (pinfunction "GPIO21_42") (pintype "passive"))
    )
    (net (code "35") (name "/GPIO22") (class "Default")
      (node (ref "U4") (pin "39") (pinfunction "GPIO22_39") (pintype "passive"))
    )
    (net (code "36") (name "/GPIO23") (class "Default")
      (node (ref "U4") (pin "36") (pinfunction "GPIO23_36") (pintype "passive"))
    )
    (net (code "37") (name "/GPIO25") (class "Default")
      (node (ref "U4") (pin "14") (pinfunction "GPIO_25_14") (pintype "passive"))
    )
    (net (code "38") (name "/GPIO26") (class "Default")
      (node (ref "U4") (pin "15") (pinfunction "GPIO_26_15") (pintype "passive"))
    )
    (net (code "39") (name "/GPIO27") (class "Default")
      (node (ref "U4") (pin "16") (pinfunction "GPIO_27_16") (pintype "passive"))
    )
    (net (code "40") (name "/GPIO32") (class "Default")
      (node (ref "R40") (pin "2") (pinfunction "2_2") (pintype "passive"))
      (node (ref "U4") (pin "12") (pinfunction "32K_XP_12") (pintype "passive"))
    )
    (net (code "41") (name "/GPIO33") (class "Default")
      (node (ref "R41") (pin "2") (pinfunction "2_2") (pintype "passive"))
      (node (ref "U4") (pin "13") (pinfunction "32K_XN_13") (pintype "passive"))
    )
    (net (code "42") (name "/GPIO34") (class "Default")
      (node (ref "R38") (pin "2") (pinfunction "2_2") (pintype "passive"))
      (node (ref "U4") (pin "10") (pinfunction "VDET_1_10") (pintype "passive"))
    )
    (net (code "43") (name "/GPIO35") (class "Default")
      (node (ref "R39") (pin "2") (pinfunction "2_2") (pintype "passive"))
      (node (ref "U4") (pin "11") (pinfunction "VDET_2_11") (pintype "passive"))
    )
    (net (code "44") (name "/GPIO36") (class "Default")
      (node (ref "C15") (pin "2") (pinfunction "2_2") (pintype "passive"))
      (node (ref "R33") (pin "2") (pinfunction "2_2") (pintype "passive"))
      (node (ref "U4") (pin "5") (pinfunction "SENSOR_VP_5") (pintype "passive"))
    )
    (net (code "45") (name "/GPIO37") (class "Default")
      (node (ref "C15") (pin "1") (pinfunction "1_1") (pintype "passive"))
      (node (ref "R34") (pin "2") (pinfunction "2_2") (pintype "passive"))
      (node (ref "U4") (pin "6") (pinfunction "SENSOR_CAPP_6") (pintype "passive"))
    )
    (net (code "46") (name "/GPIO38") (class "Default")
      (node (ref "C16") (pin "2") (pinfunction "2_2") (pintype "passive"))
      (node (ref "R46") (pin "2") (pinfunction "2_2") (pintype "passive"))
      (node (ref "U4") (pin "7") (pinfunction "SENSOR_CAPN_7") (pintype "passive"))
    )
    (net (code "47") (name "/GPIO39") (class "Default")
      (node (ref "C16") (pin "1") (pinfunction "1_1") (pintype "passive"))
      (node (ref "R47") (pin "2") (pinfunction "2_2") (pintype "passive"))
      (node (ref "U4") (pin "8") (pinfunction "SENSOR_VN_8") (pintype "passive"))
    )
    (net (code "48") (name "/SCK{slash}CLK") (class "Default")
      (node (ref "U3") (pin "6") (pinfunction "CLK_6") (pintype "passive"))
      (node (ref "U4") (pin "31") (pinfunction "SD_CLK_31") (pintype "passive"))
    )
    (net (code "49") (name "/SCS{slash}CMD") (class "Default")
      (node (ref "U3") (pin "1") (pinfunction "~{CS}_1") (pintype "passive"))
      (node (ref "U4") (pin "30") (pinfunction "SD_CMD_30") (pintype "passive"))
    )
    (net (code "50") (name "/SDI{slash}SD1") (class "Default")
      (node (ref "U3") (pin "5") (pinfunction "DI_5") (pintype "passive"))
      (node (ref "U4") (pin "33") (pinfunction "SD_DATA_1_33") (pintype "passive"))
    )
    (net (code "51") (name "/SDO{slash}SD0") (class "Default")
      (node (ref "U3") (pin "2") (pinfunction "DO_2") (pintype "passive"))
      (node (ref "U4") (pin "32") (pinfunction "SD_DATA_0_32") (pintype "passive"))
    )
    (net (code "52") (name "/SHD{slash}SD2") (class "Default")
      (node (ref "U3") (pin "7") (pinfunction "~{HOLD}_7") (pintype "passive"))
      (node (ref "U4") (pin "28") (pinfunction "SD_DATA_2_28") (pintype "passive"))
    )
    (net (code "53") (name "/SWP{slash}SD3") (class "Default")
      (node (ref "U3") (pin "3") (pinfunction "~{WP}_3") (pintype "passive"))
      (node (ref "U4") (pin "29") (pinfunction "SD_DATA_3_29") (pintype "passive"))
    )
    (net (code "54") (name "/U0RXD") (class "Default")
      (node (ref "JP2") (pin "3") (pinfunction "3_3") (pintype "passive"))
      (node (ref "U4") (pin "40") (pinfunction "U0RXD_40") (pintype "passive"))
    )
    (net (code "55") (name "/U0TXD") (class "Default")
      (node (ref "JP2") (pin "2") (pinfunction "2_2") (pintype "passive"))
      (node (ref "R8") (pin "2") (pinfunction "2_2") (pintype "passive"))
    )
    (net (code "56") (name "/VBIAS") (class "Default")
      (node (ref "R12") (pin "2") (pinfunction "2_2") (pintype "passive"))
      (node (ref "U1") (pin "10") (pinfunction "INC+_10") (pintype "passive"))
      (node (ref "U1") (pin "12") (pinfunction "IND+_12") (pintype "passive"))
      (node (ref "U1") (pin "3") (pinfunction "INA+_3") (pintype "passive"))
      (node (ref "U1") (pin "5") (pinfunction "INB+_5") (pintype "passive"))
      (node (ref "U2") (pin "10") (pinfunction "INC+_10") (pintype "passive"))
      (node (ref "U2") (pin "12") (pinfunction "IND+_12") (pintype "passive"))
      (node (ref "U2") (pin "3") (pinfunction "INA+_3") (pintype "passive"))
      (node (ref "U2") (pin "5") (pinfunction "INB+_5") (pintype "passive"))
    )
    (net (code "57") (name "/VREF2V5") (class "Default")
      (node (ref "C9") (pin "2") (pinfunction "2_2") (pintype "passive"))
      (node (ref "R12") (pin "1") (pinfunction "1_1") (pintype "passive"))
      (node (ref "U5") (pin "2") (pinfunction "OUT_2") (pintype "passive"))
    )
    (net (code "58") (name "/XTAL_N") (class "Default")
      (node (ref "C25") (pin "1") (pinfunction "1_1") (pintype "passive"))
      (node (ref "U4") (pin "44") (pinfunction "XTAL_N_44") (pintype "passive"))
      (node (ref "X1") (pin "3") (pinfunction "3_3") (pintype "passive"))
    )
    (net (code "59") (name "/XTAL_P") (class "Default")
      (node (ref "C24") (pin "1") (pinfunction "1_1") (pintype "passive"))
      (node (ref "U4") (pin "45") (pinfunction "XTAL_P_45") (pintype "passive"))
      (node (ref "X1") (pin "1") (pinfunction "1_1") (pintype "passive"))
    )
    (net (code "60") (name "GND") (class "Default")
      (node (ref "C10") (pin "1") (pinfunction "1_1") (pintype "passive"))
      (node (ref "C13") (pin "1") (pinfunction "1_1") (pintype "passive"))
      (node (ref "C14") (pin "1") (pinfunction "1_1") (pintype "passive"))
      (node (ref "C17") (pin "1") (pinfunction "1_1") (pintype "passive"))
      (node (ref "C2") (pin "1") (pinfunction "1_1") (pintype "passive"))
      (node (ref "C20") (pin "1") (pinfunction "1_1") (pintype "passive"))
      (node (ref "C21") (pin "1") (pinfunction "1_1") (pintype "passive"))
      (node (ref "C22") (pin "1") (pinfunction "1_1") (pintype "passive"))
      (node (ref "C24") (pin "2") (pinfunction "2_2") (pintype "passive"))
      (node (ref "C25") (pin "2") (pinfunction "2_2") (pintype "passive"))
      (node (ref "C26") (pin "1") (pinfunction "1_1") (pintype "passive"))
      (node (ref "C27") (pin "1") (pinfunction "1_1") (pintype "passive"))
      (node (ref "C28") (pin "1") (pinfunction "1_1") (pintype "passive"))
      (node (ref "C3") (pin "1") (pinfunction "1_1") (pintype "passive"))
      (node (ref "C4") (pin "1") (pinfunction "1_1") (pintype "passive"))
      (node (ref "C5") (pin "1") (pinfunction "1_1") (pintype "passive"))
      (node (ref "C6") (pin "1") (pinfunction "1_1") (pintype "passive"))
      (node (ref "C7") (pin "1") (pinfunction "1_1") (pintype "passive"))
      (node (ref "C8") (pin "1") (pinfunction "1_1") (pintype "passive"))
      (node (ref "C9") (pin "1") (pinfunction "1_1") (pintype "passive"))
      (node (ref "JP1") (pin "10") (pinfunction "10_10") (pintype "passive"))
      (node (ref "JP1") (pin "12") (pinfunction "12_12") (pintype "passive"))
      (node (ref "JP1") (pin "14") (pinfunction "14_14") (pintype "passive"))
      (node (ref "JP1") (pin "16") (pinfunction "16_16") (pintype "passive"))
      (node (ref "JP1") (pin "2") (pinfunction "2_2") (pintype "passive"))
      (node (ref "JP1") (pin "4") (pinfunction "4_4") (pintype "passive"))
      (node (ref "JP1") (pin "6") (pinfunction "6_6") (pintype "passive"))
      (node (ref "JP1") (pin "8") (pinfunction "8_8") (pintype "passive"))
      (node (ref "JP2") (pin "4") (pinfunction "4_4") (pintype "passive"))
      (node (ref "L2") (pin "1") (pinfunction "1_1") (pintype "passive"))
      (node (ref "R17") (pin "2") (pinfunction "2_2") (pintype "passive"))
      (node (ref "R22") (pin "2") (pinfunction "2_2") (pintype "passive"))
      (node (ref "R23") (pin "2") (pinfunction "2_2") (pintype "passive"))
      (node (ref "R31") (pin "2") (pinfunction "2_2") (pintype "passive"))
      (node (ref "R32") (pin "2") (pinfunction "2_2") (pintype "passive"))
      (node (ref "R44") (pin "2") (pinfunction "2_2") (pintype "passive"))
      (node (ref "R45") (pin "2") (pinfunction "2_2") (pintype "passive"))
      (node (ref "R5") (pin "2") (pinfunction "2_2") (pintype "passive"))
      (node (ref "SW1") (pin "2") (pinfunction "2_2") (pintype "passive"))
      (node (ref "SW2") (pin "2") (pinfunction "2_2") (pintype "passive"))
      (node (ref "TP13") (pin "1") (pinfunction "1_1") (pintype "passive"))
      (node (ref "U1") (pin "11") (pinfunction "V-_11") (pintype "passive"))
      (node (ref "U2") (pin "11") (pinfunction "V-_11") (pintype "passive"))
      (node (ref "U3") (pin "4") (pinfunction "GND_4") (pintype "passive"))
      (node (ref "U4") (pin "49") (pinfunction "GND_49") (pintype "passive"))
      (node (ref "U5") (pin "3") (pinfunction "GND_3") (pintype "passive"))
      (node (ref "X1") (pin "2") (pinfunction "2_2") (pintype "passive"))
      (node (ref "X1") (pin "4") (pinfunction "4_4") (pintype "passive"))
    )
    (net (code "61") (name "Net-(A1-ANT)") (class "Default")
      (node (ref "A1") (pin "1") (pinfunction "ANT_1") (pintype "passive"))
      (node (ref "C12") (pin "1") (pinfunction "1_1") (pintype "passive"))
      (node (ref "C14") (pin "2") (pinfunction "2_2") (pintype "passive"))
    )
    (net (code "62") (name "Net-(C12-Pad2)") (class "Default")
      (node (ref "C12") (pin "2") (pinfunction "2_2") (pintype "passive"))
      (node (ref "L2") (pin "2") (pinfunction "2_2") (pintype "passive"))
      (node (ref "R14") (pin "1") (pinfunction "1_1") (pintype "passive"))
    )
    (net (code "63") (name "Net-(JP1-Pad1)") (class "Default")
      (node (ref "JP1") (pin "1") (pinfunction "1_1") (pintype "passive"))
      (node (ref "R26") (pin "1") (pinfunction "1_1") (pintype "passive"))
    )
    (net (code "64") (name "Net-(JP1-Pad3)") (class "Default")
      (node (ref "JP1") (pin "3") (pinfunction "3_3") (pintype "passive"))
      (node (ref "R25") (pin "1") (pinfunction "1_1") (pintype "passive"))
    )
    (net (code "65") (name "Net-(JP1-Pad5)") (class "Default")
      (node (ref "JP1") (pin "5") (pinfunction "5_5") (pintype "passive"))
      (node (ref "R13") (pin "1") (pinfunction "1_1") (pintype "passive"))
    )
    (net (code "66") (name "Net-(JP1-Pad7)") (class "Default")
      (node (ref "JP1") (pin "7") (pinfunction "7_7") (pintype "passive"))
      (node (ref "R11") (pin "1") (pinfunction "1_1") (pintype "passive"))
    )
    (net (code "67") (name "Net-(JP1-Pad9)") (class "Default")
      (node (ref "JP1") (pin "9") (pinfunction "9_9") (pintype "passive"))
      (node (ref "R7") (pin "1") (pinfunction "1_1") (pintype "passive"))
    )
    (net (code "68") (name "Net-(JP1-Pad11)") (class "Default")
      (node (ref "JP1") (pin "11") (pinfunction "11_11") (pintype "passive"))
      (node (ref "R6") (pin "1") (pinfunction "1_1") (pintype "passive"))
    )
    (net (code "69") (name "Net-(JP1-Pad13)") (class "Default")
      (node (ref "JP1") (pin "13") (pinfunction "13_13") (pintype "passive"))
      (node (ref "R4") (pin "1") (pinfunction "1_1") (pintype "passive"))
    )
    (net (code "70") (name "Net-(JP1-Pad15)") (class "Default")
      (node (ref "JP1") (pin "15") (pinfunction "15_15") (pintype "passive"))
      (node (ref "R1") (pin "1") (pinfunction "1_1") (pintype "passive"))
    )
    (net (code "71") (name "Net-(LED1-K)") (class "Default")
      (node (ref "LED1") (pin "2") (pinfunction "K_2") (pintype "passive"))
      (node (ref "R37") (pin "2") (pinfunction "2_2") (pintype "passive"))
    )
    (net (code "72") (name "Net-(R2-Pad1)") (class "Default")
      (node (ref "R2") (pin "1") (pinfunction "1_1") (pintype "passive"))
      (node (ref "R3") (pin "2") (pinfunction "2_2") (pintype "passive"))
      (node (ref "R5") (pin "1") (pinfunction "1_1") (pintype "passive"))
    )
    (net (code "73") (name "Net-(R15-Pad1)") (class "Default")
      (node (ref "R15") (pin "1") (pinfunction "1_1") (pintype "passive"))
      (node (ref "R16") (pin "2") (pinfunction "2_2") (pintype "passive"))
      (node (ref "R17") (pin "1") (pinfunction "1_1") (pintype "passive"))
    )
    (net (code "74") (name "Net-(R18-Pad1)") (class "Default")
      (node (ref "R18") (pin "1") (pinfunction "1_1") (pintype "passive"))
      (node (ref "R19") (pin "2") (pinfunction "2_2") (pintype "passive"))
      (node (ref "R22") (pin "1") (pinfunction "1_1") (pintype "passive"))
    )
    (net (code "75") (name "Net-(R20-Pad1)") (class "Default")
      (node (ref "R20") (pin "1") (pinfunction "1_1") (pintype "passive"))
      (node (ref "R21") (pin "2") (pinfunction "2_2") (pintype "passive"))
      (node (ref "R23") (pin "1") (pinfunction "1_1") (pintype "passive"))
    )
    (net (code "76") (name "Net-(R27-Pad1)") (class "Default")
      (node (ref "R27") (pin "1") (pinfunction "1_1") (pintype "passive"))
      (node (ref "R28") (pin "2") (pinfunction "2_2") (pintype "passive"))
      (node (ref "R31") (pin "1") (pinfunction "1_1") (pintype "passive"))
    )
    (net (code "77") (name "Net-(R29-Pad1)") (class "Default")
      (node (ref "R29") (pin "1") (pinfunction "1_1") (pintype "passive"))
      (node (ref "R30") (pin "2") (pinfunction "2_2") (pintype "passive"))
      (node (ref "R32") (pin "1") (pinfunction "1_1") (pintype "passive"))
    )
    (net (code "78") (name "Net-(R35-Pad1)") (class "Default")
      (node (ref "R35") (pin "1") (pinfunction "1_1") (pintype "passive"))
      (node (ref "R36") (pin "2") (pinfunction "2_2") (pintype "passive"))
      (node (ref "R44") (pin "1") (pinfunction "1_1") (pintype "passive"))
    )
    (net (code "79") (name "Net-(R42-Pad1)") (class "Default")
      (node (ref "R42") (pin "1") (pinfunction "1_1") (pintype "passive"))
      (node (ref "R43") (pin "2") (pinfunction "2_2") (pintype "passive"))
      (node (ref "R45") (pin "1") (pinfunction "1_1") (pintype "passive"))
    )
    (net (code "80") (name "Net-(U4-LNA_IN)") (class "Default")
      (node (ref "R14") (pin "2") (pinfunction "2_2") (pintype "passive"))
      (node (ref "U4") (pin "2") (pinfunction "LNA_IN_2") (pintype "passive"))
    )
    (net (code "81") (name "Net-(U4-U0TXD)") (class "Default")
      (node (ref "R8") (pin "1") (pinfunction "1_1") (pintype "passive"))
      (node (ref "U4") (pin "41") (pinfunction "U0TXD_41") (pintype "passive"))
    )
    (net (code "82") (name "VDD_SDIO") (class "Default")
      (node (ref "C17") (pin "2") (pinfunction "2_2") (pintype "passive"))
      (node (ref "U3") (pin "8") (pinfunction "VCC_8") (pintype "passive"))
      (node (ref "U4") (pin "26") (pinfunction "VDD_SDIO_26") (pintype "passive"))
    )
    (net (code "83") (name "unconnected-(A1-GND-Pad2)") (class "Default")
      (node (ref "A1") (pin "2") (pinfunction "GND_2") (pintype "passive+no_connect"))
    )
  )
)
